# 3x7seg-driver.net
KiCad netlist of a schematic drawn in EAGLE
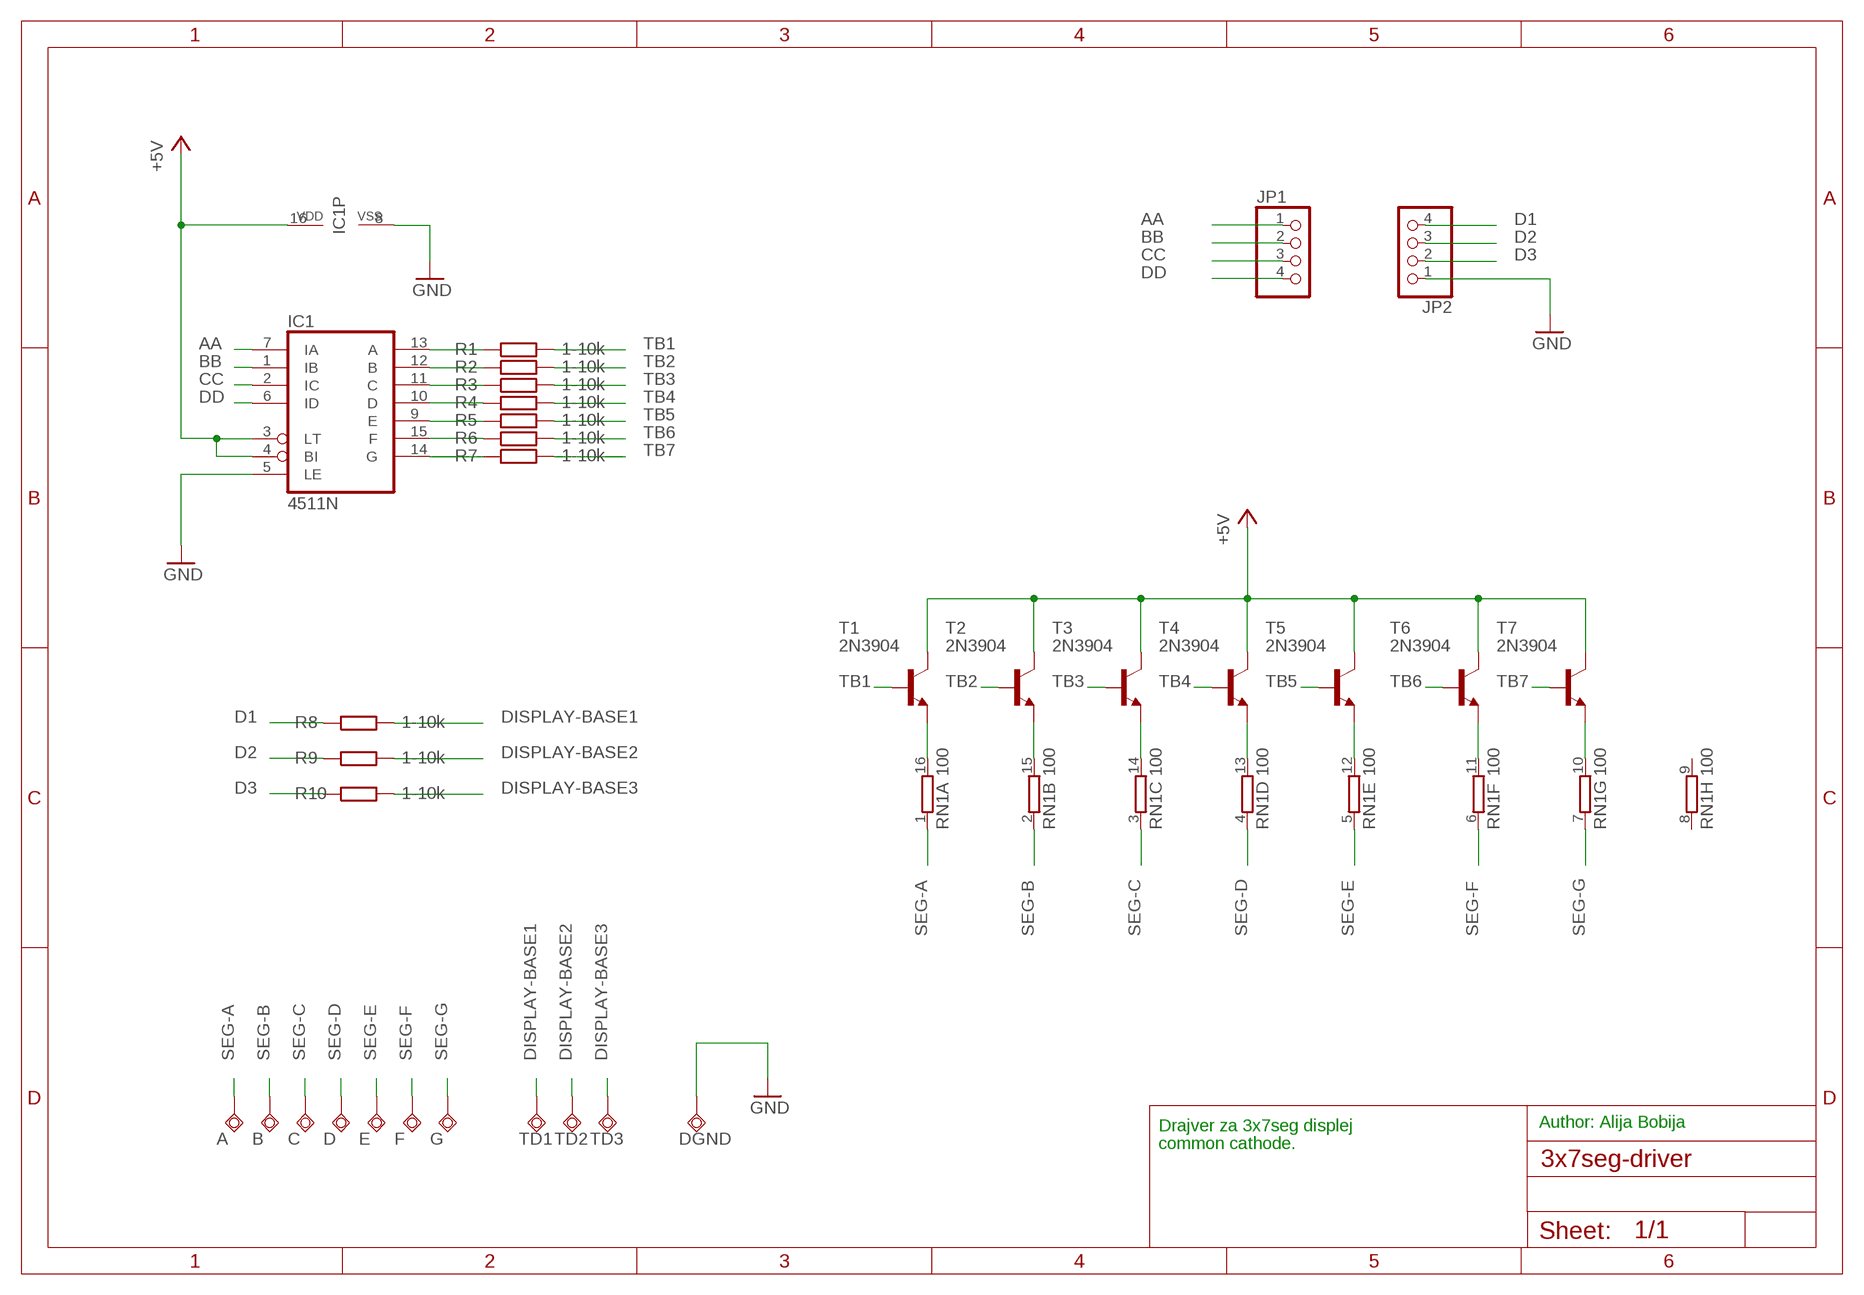
[diagram p0: schematic, sheet 1]

(export (version "E")
  (design (tool "Eeschema 10.0.6"))
  (components
    (comp (ref "A")
      (value "TPSQTP20SQ")
      (footprint "eagle-import:TP20SQ")
      (libsource (lib "eagle-import") (part "TPSQTP20SQ"))
    )
    (comp (ref "B")
      (value "TPSQTP20SQ")
      (footprint "eagle-import:TP20SQ")
      (libsource (lib "eagle-import") (part "TPSQTP20SQ"))
    )
    (comp (ref "C")
      (value "TPSQTP20SQ")
      (footprint "eagle-import:TP20SQ")
      (libsource (lib "eagle-import") (part "TPSQTP20SQ"))
    )
    (comp (ref "D")
      (value "TPSQTP20SQ")
      (footprint "eagle-import:TP20SQ")
      (libsource (lib "eagle-import") (part "TPSQTP20SQ"))
    )
    (comp (ref "DGND")
      (value "TPSQTP20SQ")
      (footprint "eagle-import:TP20SQ")
      (libsource (lib "eagle-import") (part "TPSQTP20SQ"))
    )
    (comp (ref "E")
      (value "TPSQTP20SQ")
      (footprint "eagle-import:TP20SQ")
      (libsource (lib "eagle-import") (part "TPSQTP20SQ"))
    )
    (comp (ref "F")
      (value "TPSQTP20SQ")
      (footprint "eagle-import:TP20SQ")
      (libsource (lib "eagle-import") (part "TPSQTP20SQ"))
    )
    (comp (ref "G")
      (value "TPSQTP20SQ")
      (footprint "eagle-import:TP20SQ")
      (libsource (lib "eagle-import") (part "TPSQTP20SQ"))
    )
    (comp (ref "IC1")
      (value "4511N")
      (footprint "eagle-import:DIL16")
      (libsource (lib "eagle-import") (part "4511N"))
    )
    (comp (ref "JP1")
      (value "PINHD-1X4/90")
      (footprint "eagle-import:1X04_90")
      (libsource (lib "eagle-import") (part "PINHD-1X4/90"))
    )
    (comp (ref "JP2")
      (value "PINHD-1X4/90")
      (footprint "eagle-import:1X04_90")
      (libsource (lib "eagle-import") (part "PINHD-1X4/90"))
    )
    (comp (ref "R1")
      (value "1-10k")
      (footprint "eagle-import:0207_7")
      (libsource (lib "eagle-import") (part "R-EU_0207/7"))
    )
    (comp (ref "R2")
      (value "1-10k")
      (footprint "eagle-import:0207_7")
      (libsource (lib "eagle-import") (part "R-EU_0207/7"))
    )
    (comp (ref "R3")
      (value "1-10k")
      (footprint "eagle-import:0207_7")
      (libsource (lib "eagle-import") (part "R-EU_0207/7"))
    )
    (comp (ref "R4")
      (value "1-10k")
      (footprint "eagle-import:0207_7")
      (libsource (lib "eagle-import") (part "R-EU_0207/7"))
    )
    (comp (ref "R5")
      (value "1-10k")
      (footprint "eagle-import:0207_7")
      (libsource (lib "eagle-import") (part "R-EU_0207/7"))
    )
    (comp (ref "R6")
      (value "1-10k")
      (footprint "eagle-import:0207_7")
      (libsource (lib "eagle-import") (part "R-EU_0207/7"))
    )
    (comp (ref "R7")
      (value "1-10k")
      (footprint "eagle-import:0207_7")
      (libsource (lib "eagle-import") (part "R-EU_0207/7"))
    )
    (comp (ref "R8")
      (value "1-10k")
      (footprint "eagle-import:0207_7")
      (libsource (lib "eagle-import") (part "R-EU_0207/7"))
    )
    (comp (ref "R9")
      (value "1-10k")
      (footprint "eagle-import:0207_7")
      (libsource (lib "eagle-import") (part "R-EU_0207/7"))
    )
    (comp (ref "R10")
      (value "1-10k")
      (footprint "eagle-import:0207_7")
      (libsource (lib "eagle-import") (part "R-EU_0207/7"))
    )
    (comp (ref "RN1")
      (value "100")
      (footprint "eagle-import:DIL16")
      (libsource (lib "eagle-import") (part "8R-N"))
    )
    (comp (ref "T1")
      (value "2N3904")
      (footprint "eagle-import:SOT23-EBC")
      (libsource (lib "eagle-import") (part "-NPN-SOT23-EBC"))
    )
    (comp (ref "T2")
      (value "2N3904")
      (footprint "eagle-import:SOT23-EBC")
      (libsource (lib "eagle-import") (part "-NPN-SOT23-EBC"))
    )
    (comp (ref "T3")
      (value "2N3904")
      (footprint "eagle-import:SOT23-EBC")
      (libsource (lib "eagle-import") (part "-NPN-SOT23-EBC"))
    )
    (comp (ref "T4")
      (value "2N3904")
      (footprint "eagle-import:SOT23-EBC")
      (libsource (lib "eagle-import") (part "-NPN-SOT23-EBC"))
    )
    (comp (ref "T5")
      (value "2N3904")
      (footprint "eagle-import:SOT23-EBC")
      (libsource (lib "eagle-import") (part "-NPN-SOT23-EBC"))
    )
    (comp (ref "T6")
      (value "2N3904")
      (footprint "eagle-import:SOT23-EBC")
      (libsource (lib "eagle-import") (part "-NPN-SOT23-EBC"))
    )
    (comp (ref "T7")
      (value "2N3904")
      (footprint "eagle-import:SOT23-EBC")
      (libsource (lib "eagle-import") (part "-NPN-SOT23-EBC"))
    )
    (comp (ref "TD1")
      (value "TPSQTP20SQ")
      (footprint "eagle-import:TP20SQ")
      (libsource (lib "eagle-import") (part "TPSQTP20SQ"))
    )
    (comp (ref "TD2")
      (value "TPSQTP20SQ")
      (footprint "eagle-import:TP20SQ")
      (libsource (lib "eagle-import") (part "TPSQTP20SQ"))
    )
    (comp (ref "TD3")
      (value "TPSQTP20SQ")
      (footprint "eagle-import:TP20SQ")
      (libsource (lib "eagle-import") (part "TPSQTP20SQ"))
    )
  )
  (nets
    (net (code "1") (name "+5V") (class "Default")
      (node (ref "IC1") (pin "16") (pinfunction "VDD_16") (pintype "power_in"))
      (node (ref "IC1") (pin "3") (pinfunction "LT_3") (pintype "input"))
      (node (ref "IC1") (pin "4") (pinfunction "BI_4") (pintype "input"))
      (node (ref "T1") (pin "C") (pinfunction "C_C") (pintype "passive"))
      (node (ref "T2") (pin "C") (pinfunction "C_C") (pintype "passive"))
      (node (ref "T3") (pin "C") (pinfunction "C_C") (pintype "passive"))
      (node (ref "T4") (pin "C") (pinfunction "C_C") (pintype "passive"))
      (node (ref "T5") (pin "C") (pinfunction "C_C") (pintype "passive"))
      (node (ref "T6") (pin "C") (pinfunction "C_C") (pintype "passive"))
      (node (ref "T7") (pin "C") (pinfunction "C_C") (pintype "passive"))
    )
    (net (code "2") (name "/AA") (class "Default")
      (node (ref "IC1") (pin "7") (pinfunction "IA_7") (pintype "input"))
      (node (ref "JP1") (pin "1") (pinfunction "1_1") (pintype "passive"))
    )
    (net (code "3") (name "/BB") (class "Default")
      (node (ref "IC1") (pin "1") (pinfunction "IB_1") (pintype "input"))
      (node (ref "JP1") (pin "2") (pinfunction "2_2") (pintype "passive"))
    )
    (net (code "4") (name "/CC") (class "Default")
      (node (ref "IC1") (pin "2") (pinfunction "IC_2") (pintype "input"))
      (node (ref "JP1") (pin "3") (pinfunction "3_3") (pintype "passive"))
    )
    (net (code "5") (name "/D1") (class "Default")
      (node (ref "JP2") (pin "4") (pinfunction "4_4") (pintype "passive"))
      (node (ref "R8") (pin "1") (pinfunction "1_1") (pintype "passive"))
    )
    (net (code "6") (name "/D2") (class "Default")
      (node (ref "JP2") (pin "3") (pinfunction "3_3") (pintype "passive"))
      (node (ref "R9") (pin "1") (pinfunction "1_1") (pintype "passive"))
    )
    (net (code "7") (name "/D3") (class "Default")
      (node (ref "JP2") (pin "2") (pinfunction "2_2") (pintype "passive"))
      (node (ref "R10") (pin "1") (pinfunction "1_1") (pintype "passive"))
    )
    (net (code "8") (name "/DD") (class "Default")
      (node (ref "IC1") (pin "6") (pinfunction "ID_6") (pintype "input"))
      (node (ref "JP1") (pin "4") (pinfunction "4_4") (pintype "passive"))
    )
    (net (code "9") (name "/DISPLAY-BASE1") (class "Default")
      (node (ref "R8") (pin "2") (pinfunction "2_2") (pintype "passive"))
      (node (ref "TD1") (pin "TP") (pinfunction "TP_TP") (pintype "input"))
    )
    (net (code "10") (name "/DISPLAY-BASE2") (class "Default")
      (node (ref "R9") (pin "2") (pinfunction "2_2") (pintype "passive"))
      (node (ref "TD2") (pin "TP") (pinfunction "TP_TP") (pintype "input"))
    )
    (net (code "11") (name "/DISPLAY-BASE3") (class "Default")
      (node (ref "R10") (pin "2") (pinfunction "2_2") (pintype "passive"))
      (node (ref "TD3") (pin "TP") (pinfunction "TP_TP") (pintype "input"))
    )
    (net (code "12") (name "/SEG-A") (class "Default")
      (node (ref "A") (pin "TP") (pinfunction "TP_TP") (pintype "input"))
      (node (ref "RN1") (pin "1") (pinfunction "1_1") (pintype "passive"))
    )
    (net (code "13") (name "/SEG-B") (class "Default")
      (node (ref "B") (pin "TP") (pinfunction "TP_TP") (pintype "input"))
      (node (ref "RN1") (pin "2") (pinfunction "1_2") (pintype "passive"))
    )
    (net (code "14") (name "/SEG-C") (class "Default")
      (node (ref "C") (pin "TP") (pinfunction "TP_TP") (pintype "input"))
      (node (ref "RN1") (pin "3") (pinfunction "1_3") (pintype "passive"))
    )
    (net (code "15") (name "/SEG-D") (class "Default")
      (node (ref "D") (pin "TP") (pinfunction "TP_TP") (pintype "input"))
      (node (ref "RN1") (pin "4") (pinfunction "1_4") (pintype "passive"))
    )
    (net (code "16") (name "/SEG-E") (class "Default")
      (node (ref "E") (pin "TP") (pinfunction "TP_TP") (pintype "input"))
      (node (ref "RN1") (pin "5") (pinfunction "1_5") (pintype "passive"))
    )
    (net (code "17") (name "/SEG-F") (class "Default")
      (node (ref "F") (pin "TP") (pinfunction "TP_TP") (pintype "input"))
      (node (ref "RN1") (pin "6") (pinfunction "1_6") (pintype "passive"))
    )
    (net (code "18") (name "/SEG-G") (class "Default")
      (node (ref "G") (pin "TP") (pinfunction "TP_TP") (pintype "input"))
      (node (ref "RN1") (pin "7") (pinfunction "1_7") (pintype "passive"))
    )
    (net (code "19") (name "/TB1") (class "Default")
      (node (ref "R1") (pin "2") (pinfunction "2_2") (pintype "passive"))
      (node (ref "T1") (pin "B") (pinfunction "B_B") (pintype "passive"))
    )
    (net (code "20") (name "/TB2") (class "Default")
      (node (ref "R2") (pin "2") (pinfunction "2_2") (pintype "passive"))
      (node (ref "T2") (pin "B") (pinfunction "B_B") (pintype "passive"))
    )
    (net (code "21") (name "/TB3") (class "Default")
      (node (ref "R3") (pin "2") (pinfunction "2_2") (pintype "passive"))
      (node (ref "T3") (pin "B") (pinfunction "B_B") (pintype "passive"))
    )
    (net (code "22") (name "/TB4") (class "Default")
      (node (ref "R4") (pin "2") (pinfunction "2_2") (pintype "passive"))
      (node (ref "T4") (pin "B") (pinfunction "B_B") (pintype "passive"))
    )
    (net (code "23") (name "/TB5") (class "Default")
      (node (ref "R5") (pin "2") (pinfunction "2_2") (pintype "passive"))
      (node (ref "T5") (pin "B") (pinfunction "B_B") (pintype "passive"))
    )
    (net (code "24") (name "/TB6") (class "Default")
      (node (ref "R6") (pin "2") (pinfunction "2_2") (pintype "passive"))
      (node (ref "T6") (pin "B") (pinfunction "B_B") (pintype "passive"))
    )
    (net (code "25") (name "/TB7") (class "Default")
      (node (ref "R7") (pin "2") (pinfunction "2_2") (pintype "passive"))
      (node (ref "T7") (pin "B") (pinfunction "B_B") (pintype "passive"))
    )
    (net (code "26") (name "GND") (class "Default")
      (node (ref "DGND") (pin "TP") (pinfunction "TP_TP") (pintype "input"))
      (node (ref "IC1") (pin "5") (pinfunction "LE_5") (pintype "input"))
      (node (ref "IC1") (pin "8") (pinfunction "VSS_8") (pintype "power_in"))
      (node (ref "JP2") (pin "1") (pinfunction "1_1") (pintype "passive"))
    )
    (net (code "27") (name "Net-(IC1A-A)") (class "Default")
      (node (ref "IC1") (pin "13") (pinfunction "A_13") (pintype "output"))
      (node (ref "R1") (pin "1") (pinfunction "1_1") (pintype "passive"))
    )
    (net (code "28") (name "Net-(IC1A-B)") (class "Default")
      (node (ref "IC1") (pin "12") (pinfunction "B_12") (pintype "output"))
      (node (ref "R2") (pin "1") (pinfunction "1_1") (pintype "passive"))
    )
    (net (code "29") (name "Net-(IC1A-C)") (class "Default")
      (node (ref "IC1") (pin "11") (pinfunction "C_11") (pintype "output"))
      (node (ref "R3") (pin "1") (pinfunction "1_1") (pintype "passive"))
    )
    (net (code "30") (name "Net-(IC1A-D)") (class "Default")
      (node (ref "IC1") (pin "10") (pinfunction "D_10") (pintype "output"))
      (node (ref "R4") (pin "1") (pinfunction "1_1") (pintype "passive"))
    )
    (net (code "31") (name "Net-(IC1A-E)") (class "Default")
      (node (ref "IC1") (pin "9") (pinfunction "E_9") (pintype "output"))
      (node (ref "R5") (pin "1") (pinfunction "1_1") (pintype "passive"))
    )
    (net (code "32") (name "Net-(IC1A-F)") (class "Default")
      (node (ref "IC1") (pin "15") (pinfunction "F_15") (pintype "output"))
      (node (ref "R6") (pin "1") (pinfunction "1_1") (pintype "passive"))
    )
    (net (code "33") (name "Net-(IC1A-G)") (class "Default")
      (node (ref "IC1") (pin "14") (pinfunction "G_14") (pintype "output"))
      (node (ref "R7") (pin "1") (pinfunction "1_1") (pintype "passive"))
    )
    (net (code "34") (name "Net-(RN1A-2)") (class "Default")
      (node (ref "RN1") (pin "16") (pinfunction "2_16") (pintype "passive"))
      (node (ref "T1") (pin "E") (pinfunction "E_E") (pintype "passive"))
    )
    (net (code "35") (name "Net-(RN1B-2)") (class "Default")
      (node (ref "RN1") (pin "15") (pinfunction "2_15") (pintype "passive"))
      (node (ref "T2") (pin "E") (pinfunction "E_E") (pintype "passive"))
    )
    (net (code "36") (name "Net-(RN1C-2)") (class "Default")
      (node (ref "RN1") (pin "14") (pinfunction "2_14") (pintype "passive"))
      (node (ref "T3") (pin "E") (pinfunction "E_E") (pintype "passive"))
    )
    (net (code "37") (name "Net-(RN1D-2)") (class "Default")
      (node (ref "RN1") (pin "13") (pinfunction "2_13") (pintype "passive"))
      (node (ref "T4") (pin "E") (pinfunction "E_E") (pintype "passive"))
    )
    (net (code "38") (name "Net-(RN1E-2)") (class "Default")
      (node (ref "RN1") (pin "12") (pinfunction "2_12") (pintype "passive"))
      (node (ref "T5") (pin "E") (pinfunction "E_E") (pintype "passive"))
    )
    (net (code "39") (name "Net-(RN1F-2)") (class "Default")
      (node (ref "RN1") (pin "11") (pinfunction "2_11") (pintype "passive"))
      (node (ref "T6") (pin "E") (pinfunction "E_E") (pintype "passive"))
    )
    (net (code "40") (name "Net-(RN1G-2)") (class "Default")
      (node (ref "RN1") (pin "10") (pinfunction "2_10") (pintype "passive"))
      (node (ref "T7") (pin "E") (pinfunction "E_E") (pintype "passive"))
    )
    (net (code "41") (name "unconnected-(RN1H-1-Pad8)") (class "Default")
      (node (ref "RN1") (pin "8") (pinfunction "1_8") (pintype "passive"))
    )
    (net (code "42") (name "unconnected-(RN1H-2-Pad9)") (class "Default")
      (node (ref "RN1") (pin "9") (pinfunction "2_9") (pintype "passive"))
    )
  )
)
